# Booster2.net
KiCad netlist of a schematic drawn in Altium Designer
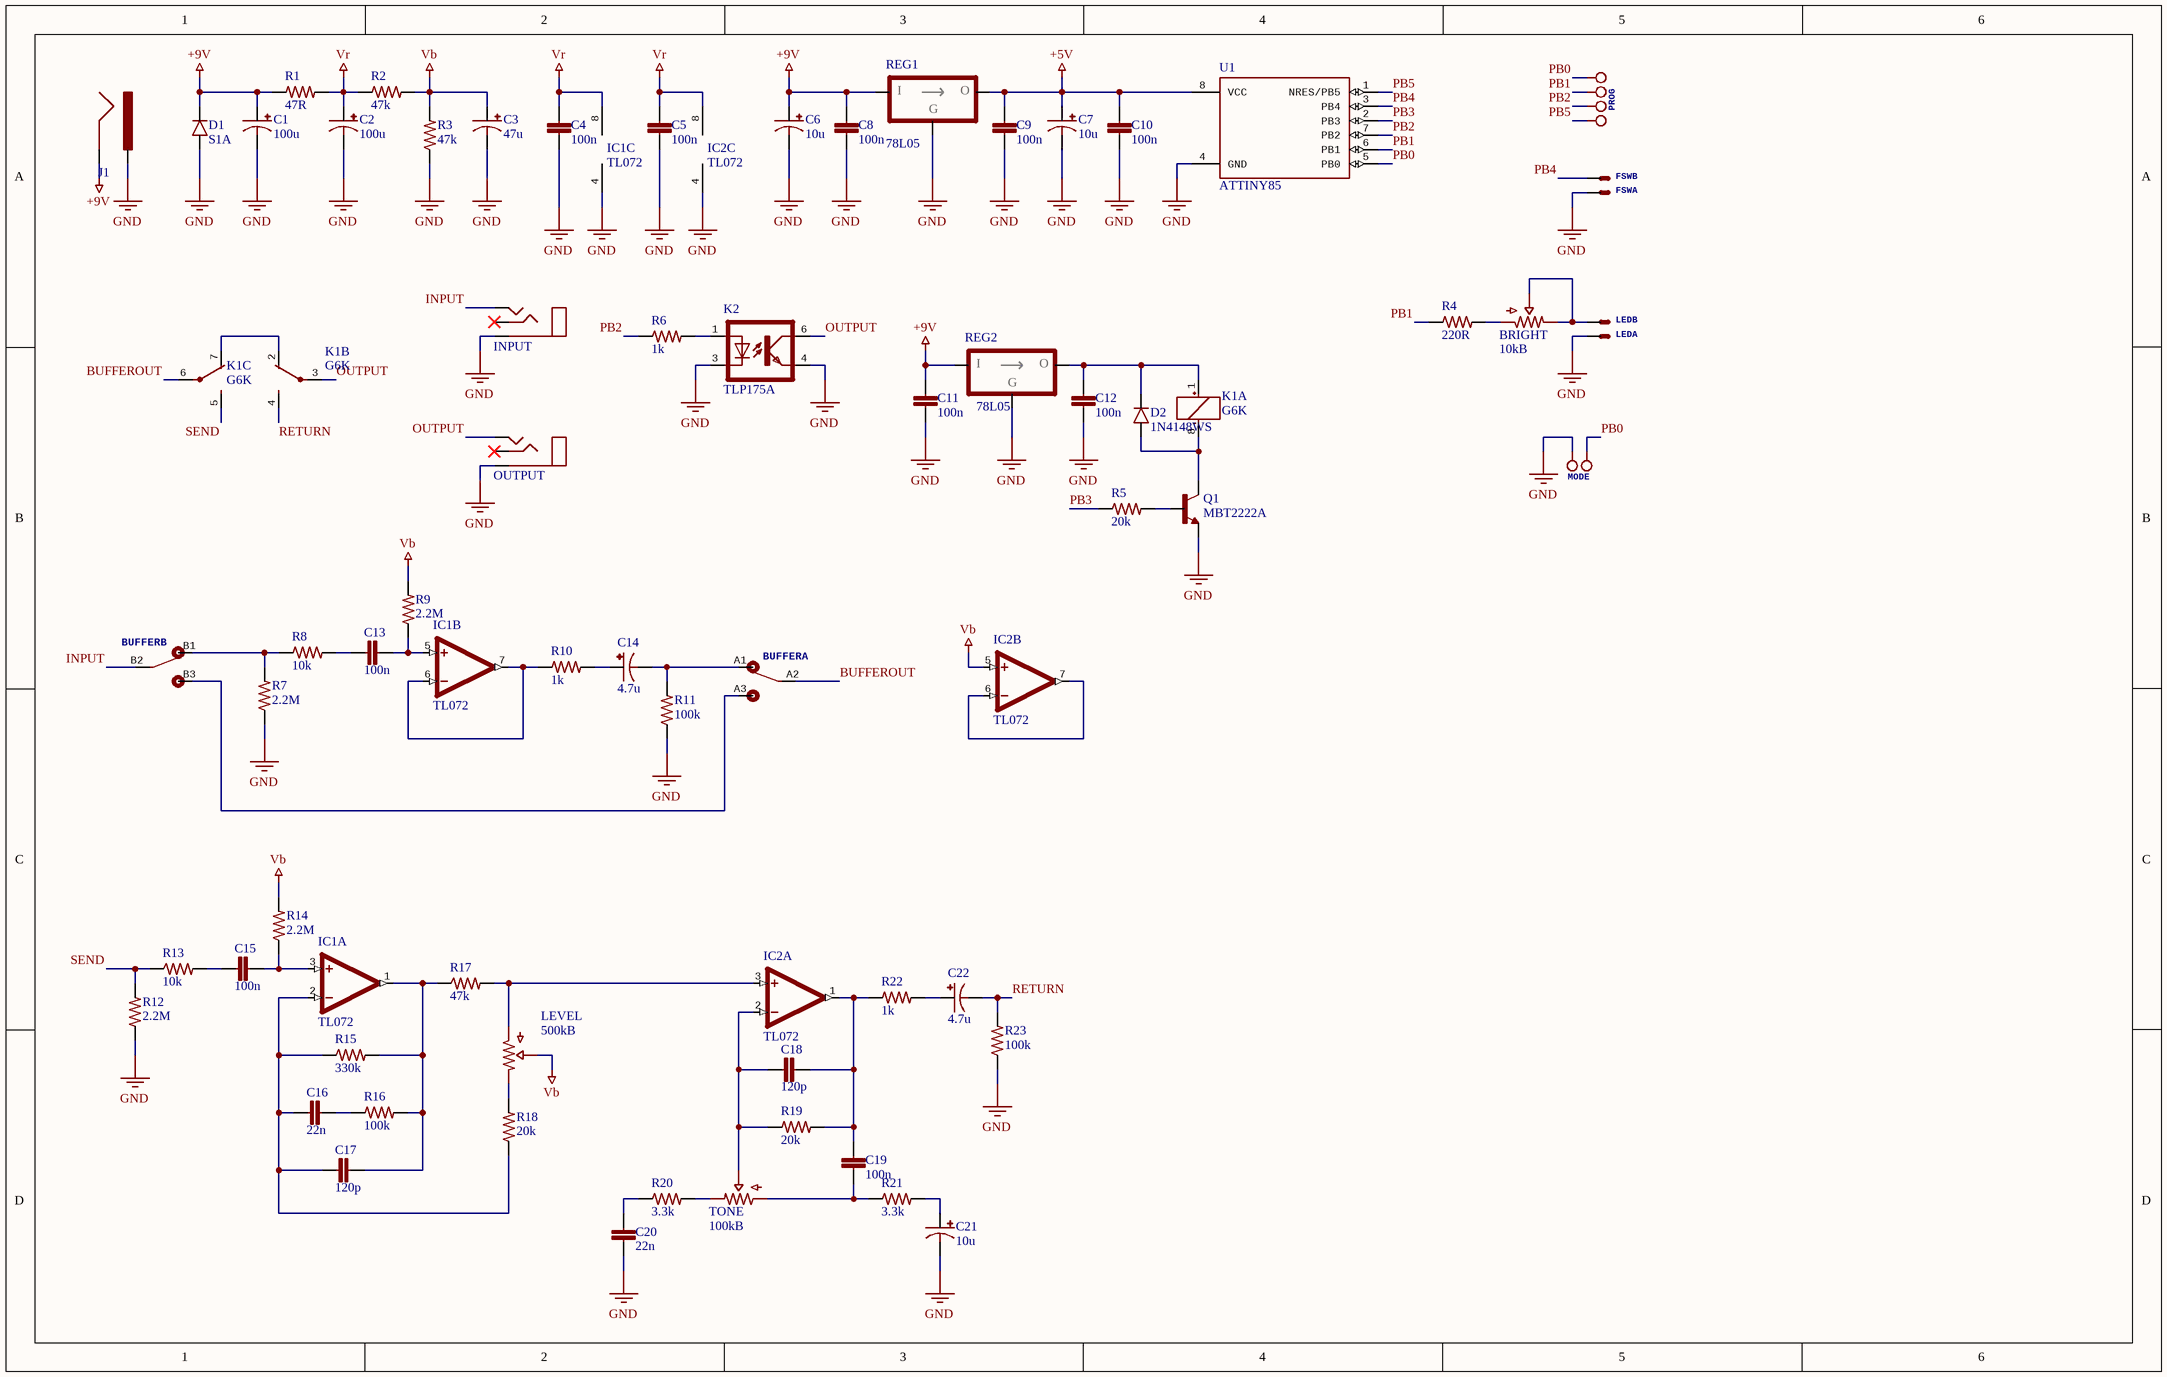
[diagram p0: Booster2.SchDoc]

(export (version "E")
  (design (tool "Eeschema 10.0.6"))
  (components
    (comp (ref "BRIGHT")
      (value "10kB")
      (footprint "BOURNS_3362P")
      (description "10k Lin 3362P trimmer")
      (libsource (lib "Pedals") (part "TRIM_10kB_3362P"))
    )
    (comp (ref "BUFFER")
      (value "DPDT")
      (footprint "DPDT_SLIDE")
      (description "DPDT slide switch ON/ON")
      (libsource (lib "Pedals") (part "SW_SLIDE_DPDT_ON-ON"))
    )
    (comp (ref "C1")
      (value "100u")
      (footprint "CAPAE_D")
      (description "CAP ALUM 100UF 25V SMD")
      (fields
        (field (name "MANUFACTURER") "Multicomp")
        (field (name "MANUFACTURER PART NUMBER") "MCVVT025M101EA6L")
      )
      (libsource (lib "Pedals SMD") (part "MCVVT025M101EA6L"))
    )
    (comp (ref "C2")
      (value "100u")
      (footprint "CAPAE_D")
      (description "CAP ALUM 100UF 25V SMD")
      (fields
        (field (name "MANUFACTURER") "Multicomp")
        (field (name "MANUFACTURER PART NUMBER") "MCVVT025M101EA6L")
      )
      (libsource (lib "Pedals SMD") (part "MCVVT025M101EA6L"))
    )
    (comp (ref "C3")
      (value "47u")
      (footprint "CAPAE_D")
      (description "CAP ALUM 47UF 25V SMD")
      (fields
        (field (name "MANUFACTURER") "Multicomp")
        (field (name "MANUFACTURER PART NUMBER") "MCVVT025M470EA1L")
      )
      (libsource (lib "Pedals SMD") (part "MCVVT025M470EA1L"))
    )
    (comp (ref "C4")
      (value "100n")
      (footprint "CHIP_0603")
      (description "CAP CER 100NF 50V X7R 0603")
      (fields
        (field (name "MANUFACTURER") "Multicomp")
        (field (name "MANUFACTURER PART NUMBER") "MC0603B104K500CT")
      )
      (libsource (lib "Pedals SMD") (part "MC0603B104K500CT"))
    )
    (comp (ref "C5")
      (value "100n")
      (footprint "CHIP_0603")
      (description "CAP CER 100NF 50V X7R 0603")
      (fields
        (field (name "MANUFACTURER") "Multicomp")
        (field (name "MANUFACTURER PART NUMBER") "MC0603B104K500CT")
      )
      (libsource (lib "Pedals SMD") (part "MC0603B104K500CT"))
    )
    (comp (ref "C6")
      (value "10u")
      (footprint "CAPAE_B")
      (description "CAP ALUM 10UF 25V SMD")
      (fields
        (field (name "MANUFACTURER") "Multicomp")
        (field (name "MANUFACTURER PART NUMBER") "MCVVT025M100CA1L")
      )
      (libsource (lib "Pedals SMD") (part "MCVVT025M100CA1L"))
    )
    (comp (ref "C7")
      (value "10u")
      (footprint "CAPAE_B")
      (description "CAP ALUM 10UF 25V SMD")
      (fields
        (field (name "MANUFACTURER") "Multicomp")
        (field (name "MANUFACTURER PART NUMBER") "MCVVT025M100CA1L")
      )
      (libsource (lib "Pedals SMD") (part "MCVVT025M100CA1L"))
    )
    (comp (ref "C8")
      (value "100n")
      (footprint "CHIP_0603")
      (description "CAP CER 100NF 50V X7R 0603")
      (fields
        (field (name "MANUFACTURER") "Multicomp")
        (field (name "MANUFACTURER PART NUMBER") "MC0603B104K500CT")
      )
      (libsource (lib "Pedals SMD") (part "MC0603B104K500CT"))
    )
    (comp (ref "C9")
      (value "100n")
      (footprint "CHIP_0603")
      (description "CAP CER 100NF 50V X7R 0603")
      (fields
        (field (name "MANUFACTURER") "Multicomp")
        (field (name "MANUFACTURER PART NUMBER") "MC0603B104K500CT")
      )
      (libsource (lib "Pedals SMD") (part "MC0603B104K500CT"))
    )
    (comp (ref "C10")
      (value "100n")
      (footprint "CHIP_0603")
      (description "CAP CER 100NF 50V X7R 0603")
      (fields
        (field (name "MANUFACTURER") "Multicomp")
        (field (name "MANUFACTURER PART NUMBER") "MC0603B104K500CT")
      )
      (libsource (lib "Pedals SMD") (part "MC0603B104K500CT"))
    )
    (comp (ref "C11")
      (value "100n")
      (footprint "CHIP_0603")
      (description "CAP CER 100NF 50V X7R 0603")
      (fields
        (field (name "MANUFACTURER") "Multicomp")
        (field (name "MANUFACTURER PART NUMBER") "MC0603B104K500CT")
      )
      (libsource (lib "Pedals SMD") (part "MC0603B104K500CT"))
    )
    (comp (ref "C12")
      (value "100n")
      (footprint "CHIP_0603")
      (description "CAP CER 100NF 50V X7R 0603")
      (fields
        (field (name "MANUFACTURER") "Multicomp")
        (field (name "MANUFACTURER PART NUMBER") "MC0603B104K500CT")
      )
      (libsource (lib "Pedals SMD") (part "MC0603B104K500CT"))
    )
    (comp (ref "C13")
      (value "100n")
      (footprint "CHIP_1206")
      (description "CAP CER 100NF 50V C0G/NP0 1206")
      (fields
        (field (name "MANUFACTURER") "Murata")
        (field (name "MANUFACTURER PART NUMBER") "GRM31C5C1H104JA01L")
      )
      (libsource (lib "Pedals SMD") (part "GRM31C5C1H104JA01L"))
    )
    (comp (ref "C14")
      (value "4.7u")
      (footprint "CAPAE_C")
      (description "CAP ALUM 4.7UF 50V LESR SMD")
      (fields
        (field (name "MANUFACTURER") "Panasonic")
        (field (name "MANUFACTURER PART NUMBER") "EEEFC1H4R7R")
      )
      (libsource (lib "Pedals SMD") (part "EEEFC1H4R7R"))
    )
    (comp (ref "C15")
      (value "100n")
      (footprint "CHIP_1206")
      (description "CAP CER 100NF 50V C0G/NP0 1206")
      (fields
        (field (name "MANUFACTURER") "Murata")
        (field (name "MANUFACTURER PART NUMBER") "GRM31C5C1H104JA01L")
      )
      (libsource (lib "Pedals SMD") (part "GRM31C5C1H104JA01L"))
    )
    (comp (ref "C16")
      (value "22n")
      (footprint "CHIP_0805")
      (description "CAP CER 22NF 50V C0G/NP0 0805")
      (fields
        (field (name "MANUFACTURER") "Murata")
        (field (name "MANUFACTURER PART NUMBER") "GRM21B5C1H223JA01L")
      )
      (libsource (lib "Pedals SMD") (part "GRM21B5C1H223JA01L"))
    )
    (comp (ref "C17")
      (value "120p")
      (footprint "CHIP_0603")
      (description "CAP CER 120PF 50V C0G/NP0 0603")
      (fields
        (field (name "MANUFACTURER") "Multicomp")
        (field (name "MANUFACTURER PART NUMBER") "MC0603N121J500CT")
      )
      (libsource (lib "Pedals SMD") (part "MC0603N121J500CT"))
    )
    (comp (ref "C18")
      (value "120p")
      (footprint "CHIP_0603")
      (description "CAP CER 120PF 50V C0G/NP0 0603")
      (fields
        (field (name "MANUFACTURER") "Multicomp")
        (field (name "MANUFACTURER PART NUMBER") "MC0603N121J500CT")
      )
      (libsource (lib "Pedals SMD") (part "MC0603N121J500CT"))
    )
    (comp (ref "C19")
      (value "100n")
      (footprint "CHIP_1206")
      (description "CAP CER 100NF 50V C0G/NP0 1206")
      (fields
        (field (name "MANUFACTURER") "Murata")
        (field (name "MANUFACTURER PART NUMBER") "GRM31C5C1H104JA01L")
      )
      (libsource (lib "") (part "GRM31C5C1H104JA01L_1"))
    )
    (comp (ref "C20")
      (value "22n")
      (footprint "CHIP_0805")
      (description "CAP CER 22NF 50V C0G/NP0 0805")
      (fields
        (field (name "MANUFACTURER") "Murata")
        (field (name "MANUFACTURER PART NUMBER") "GRM21B5C1H223JA01L")
      )
      (libsource (lib "") (part "GRM21B5C1H223JA01L_1"))
    )
    (comp (ref "C21")
      (value "10u")
      (footprint "CAPAE_D")
      (description "CAP ALUM 10UF 20% 50V LESR SMD")
      (fields
        (field (name "MANUFACTURER") "Panasonic")
        (field (name "MANUFACTURER PART NUMBER") "EEEFC1H100P")
      )
      (libsource (lib "Pedals SMD") (part "EEEFC1H100P"))
    )
    (comp (ref "C22")
      (value "4.7u")
      (footprint "CAPAE_C")
      (description "CAP ALUM 4.7UF 50V LESR SMD")
      (fields
        (field (name "MANUFACTURER") "Panasonic")
        (field (name "MANUFACTURER PART NUMBER") "EEEFC1H4R7R")
      )
      (libsource (lib "Pedals SMD") (part "EEEFC1H4R7R"))
    )
    (comp (ref "D1")
      (value "S1A")
      (footprint "DO214")
      (description "DIODE GEN PURP 50V 1A SMA")
      (fields (field (name "MANUFACTURER") "ON Semiconductor / Fairchild"))
      (libsource (lib "Pedals SMD") (part "S1A"))
    )
    (comp (ref "D2")
      (value "1N4148WS")
      (footprint "SOD323")
      (description "DIODE GEN PURP 75V 150MA SOD323F")
      (fields (field (name "MANUFACTURER") "ON Semiconductor / Fairchild"))
      (libsource (lib "Pedals SMD") (part "1N4148WS"))
    )
    (comp (ref "FSW")
      (value "J_JST-XH-02")
      (footprint "JST-XH-02")
      (description "2 Pins male XH header")
      (libsource (lib "Pedals") (part "J_JST-XH-02"))
    )
    (comp (ref "IC1")
      (value "TL072")
      (footprint "SO-8")
      (description "IC OPAMP JFET 4MHZ 8SO")
      (fields
        (field (name "MANUFACTURER") "STMicroelectronics")
        (field (name "MANUFACTURER PART NUMBER") "TL072CDT")
      )
      (libsource (lib "Pedals SMD") (part "TL072CDT"))
    )
    (comp (ref "IC2")
      (value "TL072")
      (footprint "SO-8")
      (description "IC OPAMP JFET 4MHZ 8SO")
      (fields
        (field (name "MANUFACTURER") "STMicroelectronics")
        (field (name "MANUFACTURER PART NUMBER") "TL072CDT")
      )
      (libsource (lib "Pedals SMD") (part "TL072CDT"))
    )
    (comp (ref "INPUT")
      (value "J_STEREO")
      (footprint "STEREO")
      (description "6.35mm stereo insulated socket jack PCB mounted")
      (libsource (lib "Pedals") (part "J_STEREO"))
    )
    (comp (ref "J1")
      (value "J_DC_JACK")
      (footprint "DC_JACK")
      (description "DC Power jack 2.1mm barrel")
      (libsource (lib "Pedals") (part "J_DC_JACK"))
    )
    (comp (ref "K1")
      (value "G6K")
      (footprint "G6K")
      (description "OMRON - G6K-2F 5DC - RELAY, SIGNAL, DPDT, 30VDC, 1A")
      (fields (field (name "MANUFACTURER") "Cliff") (field (name "MANUFACTURER PART NUMBER") "G6K-2F5DC"))
      (libsource (lib "Pedals SMD") (part "G6K-2F5DC"))
    )
    (comp (ref "K2")
      (value "TLP175A")
      (footprint "TLP175A")
      (description "Toshiba TLP175A AC Input MOSFET Output Optocoupler, Surface Mount, 4-Pin SOIC")
      (fields (field (name "MANUFACTURER") "Toshiba"))
      (libsource (lib "Pedals SMD") (part "TLP175A"))
    )
    (comp (ref "LED")
      (value "J_JST-XH-02")
      (footprint "JST-XH-02")
      (description "2 Pins male XH header")
      (libsource (lib "Pedals") (part "J_JST-XH-02"))
    )
    (comp (ref "LEVEL")
      (value "500kB")
      (footprint "ALPHA_16mm_BOTTOM")
      (description "500k Lin potentiometer round shaft")
      (libsource (lib "Pedals") (part "POT_500kB_ALPHA_16mm"))
    )
    (comp (ref "MODE")
      (value "J_HEADER_2PINS")
      (footprint "HEADER_2PINS")
      (description "2 Pins male header")
      (libsource (lib "Pedals") (part "J_HEADER_2PINS"))
    )
    (comp (ref "OUTPUT")
      (value "J_STEREO")
      (footprint "STEREO")
      (description "6.35mm stereo insulated socket jack PCB mounted")
      (libsource (lib "Pedals") (part "J_STEREO"))
    )
    (comp (ref "PROG")
      (value "J_HEADER_4PINS_FEM")
      (footprint "HEADER_4Pins_FEM")
      (description "4 Pins female header")
      (libsource (lib "Pedals") (part "J_HEADER_4PINS_FEM"))
    )
    (comp (ref "Q1")
      (value "MBT2222A")
      (footprint "SOT23")
      (description "TRANS NPN 40V 0.6A SOT323")
      (fields
        (field (name "MANUFACTURER") "ON Semiconductor")
        (field (name "MANUFACTURER PART NUMBER") "MMBT2222AWT1G")
      )
      (libsource (lib "Pedals SMD") (part "MMBT2222AWT1G"))
    )
    (comp (ref "R1")
      (value "47R")
      (footprint "CHIP_R_1206")
      (description "RES SMD 47 OHM 1% 1/4W 1206")
      (fields
        (field (name "MANUFACTURER") "Vishay")
        (field (name "MANUFACTURER PART NUMBER") "CRCW120647R0FKEA")
      )
      (libsource (lib "Pedals SMD") (part "CRCW120647R0FKEA"))
    )
    (comp (ref "R2")
      (value "47k")
      (footprint "CHIP_R_1206")
      (description "RES SMD 47K OHM 1% 1/4W 1206")
      (fields
        (field (name "MANUFACTURER") "Vishay")
        (field (name "MANUFACTURER PART NUMBER") "CRCW120647K0FKEA")
      )
      (libsource (lib "Pedals SMD") (part "CRCW120647K0FKEA"))
    )
    (comp (ref "R3")
      (value "47k")
      (footprint "CHIP_R_1206")
      (description "RES SMD 47K OHM 1% 1/4W 1206")
      (fields
        (field (name "MANUFACTURER") "Vishay")
        (field (name "MANUFACTURER PART NUMBER") "CRCW120647K0FKEA")
      )
      (libsource (lib "Pedals SMD") (part "CRCW120647K0FKEA"))
    )
    (comp (ref "R4")
      (value "220R")
      (footprint "CHIP_R_1206")
      (description "RES SMD 220 OHM 1% 1/4W 1206")
      (fields
        (field (name "MANUFACTURER") "Vishay")
        (field (name "MANUFACTURER PART NUMBER") "CRCW1206220RFKEA")
      )
      (libsource (lib "Pedals SMD") (part "CRCW1206220RFKEA"))
    )
    (comp (ref "R5")
      (value "20k")
      (footprint "CHIP_R_0603")
      (description "RES SMD 20K OHM 1% 1/10W 0603")
      (fields
        (field (name "MANUFACTURER") "Vishay")
        (field (name "MANUFACTURER PART NUMBER") "CRCW060320K0FKEA")
      )
      (libsource (lib "Pedals SMD") (part "CRCW060320K0FKEA"))
    )
    (comp (ref "R6")
      (value "1k")
      (footprint "CHIP_R_0603")
      (description "RES SMD 1K OHM 1% 1/10W 0603")
      (fields
        (field (name "MANUFACTURER") "Vishay Dale")
        (field (name "MANUFACTURER PART NUMBER") "CRCW06031K00FKEA")
      )
      (libsource (lib "Pedals SMD") (part "CRCW06031K00FKEA"))
    )
    (comp (ref "R7")
      (value "2.2M")
      (footprint "CHIP_R_0603")
      (description "RES SMD 2.2M OHM 1% 1/10W 0603")
      (fields
        (field (name "MANUFACTURER") "Vishay")
        (field (name "MANUFACTURER PART NUMBER") "CRCW06032M20FKEA")
      )
      (libsource (lib "Pedals SMD") (part "CRCW06032M20FKEA"))
    )
    (comp (ref "R8")
      (value "10k")
      (footprint "CHIP_R_0603")
      (description "RES SMD 10K OHM 1% 1/10W 0603")
      (fields
        (field (name "MANUFACTURER") "Vishay")
        (field (name "MANUFACTURER PART NUMBER") "CRCW060310K0FKEA")
      )
      (libsource (lib "Pedals SMD") (part "CRCW060310K0FKEA"))
    )
    (comp (ref "R9")
      (value "2.2M")
      (footprint "CHIP_R_0603")
      (description "RES SMD 2.2M OHM 1% 1/10W 0603")
      (fields
        (field (name "MANUFACTURER") "Vishay")
        (field (name "MANUFACTURER PART NUMBER") "CRCW06032M20FKEA")
      )
      (libsource (lib "Pedals SMD") (part "CRCW06032M20FKEA"))
    )
    (comp (ref "R10")
      (value "1k")
      (footprint "CHIP_R_0603")
      (description "RES SMD 1K OHM 1% 1/10W 0603")
      (fields
        (field (name "MANUFACTURER") "Vishay Dale")
        (field (name "MANUFACTURER PART NUMBER") "CRCW06031K00FKEA")
      )
      (libsource (lib "Pedals SMD") (part "CRCW06031K00FKEA"))
    )
    (comp (ref "R11")
      (value "100k")
      (footprint "CHIP_R_0603")
      (description "RES SMD 100K OHM 1% 1/10W 0603")
      (fields
        (field (name "MANUFACTURER") "Vishay")
        (field (name "MANUFACTURER PART NUMBER") "CRCW0603100KFKEA")
      )
      (libsource (lib "Pedals SMD") (part "CRCW0603100KFKEA"))
    )
    (comp (ref "R12")
      (value "2.2M")
      (footprint "CHIP_R_0603")
      (description "RES SMD 2.2M OHM 1% 1/10W 0603")
      (fields
        (field (name "MANUFACTURER") "Vishay")
        (field (name "MANUFACTURER PART NUMBER") "CRCW06032M20FKEA")
      )
      (libsource (lib "Pedals SMD") (part "CRCW06032M20FKEA"))
    )
    (comp (ref "R13")
      (value "10k")
      (footprint "CHIP_R_0603")
      (description "RES SMD 10K OHM 1% 1/10W 0603")
      (fields
        (field (name "MANUFACTURER") "Vishay")
        (field (name "MANUFACTURER PART NUMBER") "CRCW060310K0FKEA")
      )
      (libsource (lib "Pedals SMD") (part "CRCW060310K0FKEA"))
    )
    (comp (ref "R14")
      (value "2.2M")
      (footprint "CHIP_R_0603")
      (description "RES SMD 2.2M OHM 1% 1/10W 0603")
      (fields
        (field (name "MANUFACTURER") "Vishay")
        (field (name "MANUFACTURER PART NUMBER") "CRCW06032M20FKEA")
      )
      (libsource (lib "Pedals SMD") (part "CRCW06032M20FKEA"))
    )
    (comp (ref "R15")
      (value "330k")
      (footprint "CHIP_R_0603")
      (description "RES SMD 330K OHM 1% 1/10W 0603")
      (fields
        (field (name "MANUFACTURER") "Vishay")
        (field (name "MANUFACTURER PART NUMBER") "CRCW0603330KFKEA")
      )
      (libsource (lib "Pedals SMD") (part "CRCW0603330KFKEA"))
    )
    (comp (ref "R16")
      (value "100k")
      (footprint "CHIP_R_0603")
      (description "RES SMD 100K OHM 1% 1/10W 0603")
      (fields
        (field (name "MANUFACTURER") "Vishay")
        (field (name "MANUFACTURER PART NUMBER") "CRCW0603100KFKEA")
      )
      (libsource (lib "Pedals SMD") (part "CRCW0603100KFKEA"))
    )
    (comp (ref "R17")
      (value "47k")
      (footprint "CHIP_R_0603")
      (description "RES SMD 47K OHM 1% 1/10W 0603")
      (fields
        (field (name "MANUFACTURER") "Vishay")
        (field (name "MANUFACTURER PART NUMBER") "CRCW060347K0FKEA")
      )
      (libsource (lib "Pedals SMD") (part "CRCW060347K0FKEA"))
    )
    (comp (ref "R18")
      (value "20k")
      (footprint "CHIP_R_0603")
      (description "RES SMD 20K OHM 1% 1/10W 0603")
      (fields
        (field (name "MANUFACTURER") "Vishay")
        (field (name "MANUFACTURER PART NUMBER") "CRCW060320K0FKEA")
      )
      (libsource (lib "Pedals SMD") (part "CRCW060320K0FKEA"))
    )
    (comp (ref "R19")
      (value "20k")
      (footprint "CHIP_R_0603")
      (description "RES SMD 20K OHM 1% 1/10W 0603")
      (fields
        (field (name "MANUFACTURER") "Vishay")
        (field (name "MANUFACTURER PART NUMBER") "CRCW060320K0FKEA")
      )
      (libsource (lib "Pedals SMD") (part "CRCW060320K0FKEA"))
    )
    (comp (ref "R20")
      (value "3.3k")
      (footprint "CHIP_R_0603")
      (description "RES SMD 3.3K OHM 1% 1/10W 0603")
      (fields
        (field (name "MANUFACTURER") "Vishay")
        (field (name "MANUFACTURER PART NUMBER") "CRCW06033K30FKEA")
      )
      (libsource (lib "Pedals SMD") (part "CRCW06033K30FKEA"))
    )
    (comp (ref "R21")
      (value "3.3k")
      (footprint "CHIP_R_0603")
      (description "RES SMD 3.3K OHM 1% 1/10W 0603")
      (fields
        (field (name "MANUFACTURER") "Vishay")
        (field (name "MANUFACTURER PART NUMBER") "CRCW06033K30FKEA")
      )
      (libsource (lib "Pedals SMD") (part "CRCW06033K30FKEA"))
    )
    (comp (ref "R22")
      (value "1k")
      (footprint "CHIP_R_0603")
      (description "RES SMD 1K OHM 1% 1/10W 0603")
      (fields
        (field (name "MANUFACTURER") "Vishay Dale")
        (field (name "MANUFACTURER PART NUMBER") "CRCW06031K00FKEA")
      )
      (libsource (lib "Pedals SMD") (part "CRCW06031K00FKEA"))
    )
    (comp (ref "R23")
      (value "100k")
      (footprint "CHIP_R_0603")
      (description "RES SMD 100K OHM 1% 1/10W 0603")
      (fields
        (field (name "MANUFACTURER") "Vishay")
        (field (name "MANUFACTURER PART NUMBER") "CRCW0603100KFKEA")
      )
      (libsource (lib "Pedals SMD") (part "CRCW0603100KFKEA"))
    )
    (comp (ref "REG1")
      (value "78L05")
      (footprint "SOT23-3")
      (description "TAIWAN SEMICONDUCTOR - TS78L05CX RFG - REG 3-TERMINAL 100MA, SMD, SOT23-3")
      (fields
        (field (name "MANUFACTURER") "Taiwan Semiconductor")
        (field (name "MANUFACTURER PART NUMBER") "TS78L05CXRFG")
      )
      (libsource (lib "Pedals SMD") (part "TS78L05CXRFG"))
    )
    (comp (ref "REG2")
      (value "78L05")
      (footprint "SOT23-3")
      (description "TAIWAN SEMICONDUCTOR - TS78L05CX RFG - REG 3-TERMINAL 100MA, SMD, SOT23-3")
      (fields
        (field (name "MANUFACTURER") "Taiwan Semiconductor")
        (field (name "MANUFACTURER PART NUMBER") "TS78L05CXRFG")
      )
      (libsource (lib "Pedals SMD") (part "TS78L05CXRFG"))
    )
    (comp (ref "TONE")
      (value "100kB")
      (footprint "ALPHA_16mm_BOTTOM")
      (description "100k Lin potentiometer round shaft")
      (libsource (lib "Pedals") (part "POT_100kB_ALPHA_16mm"))
    )
    (comp (ref "U1")
      (value "ATTINY85")
      (footprint "SOP8")
      (description "IC, 8BIT MCU, AVR TINY, 20MHZ, 8-SOIC")
      (fields
        (field (name "MANUFACTURER") "Microchip / Atmel")
        (field (name "MANUFACTURER PART NUMBER") "ATTINY85-20SU")
      )
      (libsource (lib "Pedals SMD") (part "ATTINY85-20SU"))
    )
  )
  (nets
    (net (code "1") (name "+5V") (class "Default")
      (node (ref "C10") (pin "1") (pinfunction "1_1") (pintype "passive"))
      (node (ref "C7") (pin "+") (pinfunction "+_+") (pintype "passive"))
      (node (ref "C9") (pin "1") (pinfunction "1_1") (pintype "passive"))
      (node (ref "REG1") (pin "1") (pinfunction "OUTPUT_1") (pintype "power_in"))
      (node (ref "U1") (pin "8") (pinfunction "VCC_8") (pintype "power_in"))
    )
    (net (code "2") (name "+9V") (class "Default")
      (node (ref "C1") (pin "+") (pinfunction "+_+") (pintype "passive"))
      (node (ref "C11") (pin "1") (pinfunction "1_1") (pintype "passive"))
      (node (ref "C6") (pin "+") (pinfunction "+_+") (pintype "passive"))
      (node (ref "C8") (pin "1") (pinfunction "1_1") (pintype "passive"))
      (node (ref "D1") (pin "1") (pinfunction "1_1") (pintype "passive"))
      (node (ref "J1") (pin "GND") (pinfunction "GND_GND") (pintype "passive"))
      (node (ref "R1") (pin "1") (pinfunction "1_1") (pintype "passive"))
      (node (ref "REG1") (pin "2") (pinfunction "INPUT_2") (pintype "power_in"))
      (node (ref "REG2") (pin "2") (pinfunction "INPUT_2") (pintype "power_in"))
    )
    (net (code "3") (name "/BUFFEROUT") (class "Default")
      (node (ref "BUFFER") (pin "A2") (pinfunction "2_A2") (pintype "passive"))
      (node (ref "K1") (pin "6") (pinfunction "P_6") (pintype "passive"))
    )
    (net (code "4") (name "/INPUT") (class "Default")
      (node (ref "BUFFER") (pin "B2") (pinfunction "2_B2") (pintype "passive"))
      (node (ref "INPUT") (pin "T") (pinfunction "T_T") (pintype "passive"))
    )
    (net (code "5") (name "/OUTPUT") (class "Default")
      (node (ref "K1") (pin "3") (pinfunction "P_3") (pintype "passive"))
      (node (ref "K2") (pin "6") (pinfunction "COL_6") (pintype "passive"))
      (node (ref "OUTPUT") (pin "T") (pinfunction "T_T") (pintype "passive"))
    )
    (net (code "6") (name "/PB0") (class "Default")
      (node (ref "MODE") (pin "2") (pinfunction "2_2") (pintype "passive"))
      (node (ref "PROG") (pin "4") (pinfunction "4_4") (pintype "passive"))
      (node (ref "U1") (pin "5") (pinfunction "PB0_5") (pintype "bidirectional"))
    )
    (net (code "7") (name "/PB1") (class "Default")
      (node (ref "PROG") (pin "3") (pinfunction "3_3") (pintype "passive"))
      (node (ref "R4") (pin "1") (pinfunction "1_1") (pintype "passive"))
      (node (ref "U1") (pin "6") (pinfunction "PB1_6") (pintype "bidirectional"))
    )
    (net (code "8") (name "/PB2") (class "Default")
      (node (ref "PROG") (pin "2") (pinfunction "2_2") (pintype "passive"))
      (node (ref "R6") (pin "1") (pinfunction "1_1") (pintype "passive"))
      (node (ref "U1") (pin "7") (pinfunction "PB2_7") (pintype "bidirectional"))
    )
    (net (code "9") (name "/PB3") (class "Default")
      (node (ref "R5") (pin "1") (pinfunction "1_1") (pintype "passive"))
      (node (ref "U1") (pin "2") (pinfunction "PB3_2") (pintype "bidirectional"))
    )
    (net (code "10") (name "/PB4") (class "Default")
      (node (ref "FSW") (pin "1") (pinfunction "S_1") (pintype "passive"))
      (node (ref "U1") (pin "3") (pinfunction "PB4_3") (pintype "bidirectional"))
    )
    (net (code "11") (name "/PB5") (class "Default")
      (node (ref "PROG") (pin "1") (pinfunction "1_1") (pintype "passive"))
      (node (ref "U1") (pin "1") (pinfunction "NRES/PB5_1") (pintype "bidirectional"))
    )
    (net (code "12") (name "/RETURN") (class "Default")
      (node (ref "C22") (pin "-") (pinfunction "-_-") (pintype "passive"))
      (node (ref "K1") (pin "4") (pinfunction "S_4") (pintype "passive"))
      (node (ref "R23") (pin "2") (pinfunction "2_2") (pintype "passive"))
    )
    (net (code "13") (name "/SEND") (class "Default")
      (node (ref "K1") (pin "5") (pinfunction "S_5") (pintype "passive"))
      (node (ref "R12") (pin "2") (pinfunction "2_2") (pintype "passive"))
      (node (ref "R13") (pin "1") (pinfunction "1_1") (pintype "passive"))
    )
    (net (code "14") (name "GND") (class "Default")
      (node (ref "C1") (pin "-") (pinfunction "-_-") (pintype "passive"))
      (node (ref "C10") (pin "2") (pinfunction "2_2") (pintype "passive"))
      (node (ref "C11") (pin "2") (pinfunction "2_2") (pintype "passive"))
      (node (ref "C12") (pin "2") (pinfunction "2_2") (pintype "passive"))
      (node (ref "C2") (pin "-") (pinfunction "-_-") (pintype "passive"))
      (node (ref "C20") (pin "2") (pinfunction "2_2") (pintype "passive"))
      (node (ref "C21") (pin "-") (pinfunction "-_-") (pintype "passive"))
      (node (ref "C3") (pin "-") (pinfunction "-_-") (pintype "passive"))
      (node (ref "C4") (pin "2") (pinfunction "2_2") (pintype "passive"))
      (node (ref "C5") (pin "2") (pinfunction "2_2") (pintype "passive"))
      (node (ref "C6") (pin "-") (pinfunction "-_-") (pintype "passive"))
      (node (ref "C7") (pin "-") (pinfunction "-_-") (pintype "passive"))
      (node (ref "C8") (pin "2") (pinfunction "2_2") (pintype "passive"))
      (node (ref "C9") (pin "2") (pinfunction "2_2") (pintype "passive"))
      (node (ref "D1") (pin "2") (pinfunction "2_2") (pintype "passive"))
      (node (ref "FSW") (pin "2") (pinfunction "S_2") (pintype "passive"))
      (node (ref "IC1") (pin "4") (pinfunction "V-_4") (pintype "power_in"))
      (node (ref "IC2") (pin "4") (pinfunction "V-_4") (pintype "power_in"))
      (node (ref "INPUT") (pin "S") (pinfunction "S_S") (pintype "passive"))
      (node (ref "J1") (pin "PWR") (pinfunction "PWR_PWR") (pintype "passive"))
      (node (ref "K2") (pin "3") (pinfunction "C_3") (pintype "passive"))
      (node (ref "K2") (pin "4") (pinfunction "EMIT_4") (pintype "passive"))
      (node (ref "LED") (pin "2") (pinfunction "S_2") (pintype "passive"))
      (node (ref "MODE") (pin "1") (pinfunction "1_1") (pintype "passive"))
      (node (ref "OUTPUT") (pin "S") (pinfunction "S_S") (pintype "passive"))
      (node (ref "Q1") (pin "2") (pinfunction "E_2") (pintype "passive"))
      (node (ref "R11") (pin "1") (pinfunction "1_1") (pintype "passive"))
      (node (ref "R12") (pin "1") (pinfunction "1_1") (pintype "passive"))
      (node (ref "R23") (pin "1") (pinfunction "1_1") (pintype "passive"))
      (node (ref "R3") (pin "1") (pinfunction "1_1") (pintype "passive"))
      (node (ref "R7") (pin "1") (pinfunction "1_1") (pintype "passive"))
      (node (ref "REG1") (pin "3") (pinfunction "COMMON_3") (pintype "power_in"))
      (node (ref "REG2") (pin "3") (pinfunction "COMMON_3") (pintype "power_in"))
      (node (ref "U1") (pin "4") (pinfunction "GND_4") (pintype "power_in"))
    )
    (net (code "15") (name "Net-(BRIGHT-Pad1)") (class "Default")
      (node (ref "BRIGHT") (pin "1") (pinfunction "1_1") (pintype "passive"))
      (node (ref "R4") (pin "2") (pinfunction "2_2") (pintype "passive"))
    )
    (net (code "16") (name "Net-(BUFFERA-1)") (class "Default")
      (node (ref "BUFFER") (pin "A1") (pinfunction "1_A1") (pintype "passive"))
      (node (ref "C14") (pin "-") (pinfunction "-_-") (pintype "passive"))
      (node (ref "R11") (pin "2") (pinfunction "2_2") (pintype "passive"))
    )
    (net (code "17") (name "Net-(BUFFERA-3)") (class "Default")
      (node (ref "BUFFER") (pin "A3") (pinfunction "3_A3") (pintype "passive"))
      (node (ref "BUFFER") (pin "B3") (pinfunction "3_B3") (pintype "passive"))
    )
    (net (code "18") (name "Net-(BUFFERB-1)") (class "Default")
      (node (ref "BUFFER") (pin "B1") (pinfunction "1_B1") (pintype "passive"))
      (node (ref "R7") (pin "2") (pinfunction "2_2") (pintype "passive"))
      (node (ref "R8") (pin "1") (pinfunction "1_1") (pintype "passive"))
    )
    (net (code "19") (name "Net-(C13-Pad2)") (class "Default")
      (node (ref "C13") (pin "2") (pinfunction "2_2") (pintype "passive"))
      (node (ref "R8") (pin "2") (pinfunction "2_2") (pintype "passive"))
    )
    (net (code "20") (name "Net-(C14-Pad+)") (class "Default")
      (node (ref "C14") (pin "+") (pinfunction "+_+") (pintype "passive"))
      (node (ref "R10") (pin "2") (pinfunction "2_2") (pintype "passive"))
    )
    (net (code "21") (name "Net-(C15-Pad2)") (class "Default")
      (node (ref "C15") (pin "2") (pinfunction "2_2") (pintype "passive"))
      (node (ref "R13") (pin "2") (pinfunction "2_2") (pintype "passive"))
    )
    (net (code "22") (name "Net-(C16-Pad1)") (class "Default")
      (node (ref "C16") (pin "1") (pinfunction "1_1") (pintype "passive"))
      (node (ref "R16") (pin "1") (pinfunction "1_1") (pintype "passive"))
    )
    (net (code "23") (name "Net-(C19-Pad2)") (class "Default")
      (node (ref "C19") (pin "2") (pinfunction "2_2") (pintype "passive"))
      (node (ref "R21") (pin "1") (pinfunction "1_1") (pintype "passive"))
      (node (ref "TONE") (pin "1") (pinfunction "1_1") (pintype "passive"))
    )
    (net (code "24") (name "Net-(C20-Pad1)") (class "Default")
      (node (ref "C20") (pin "1") (pinfunction "1_1") (pintype "passive"))
      (node (ref "R20") (pin "1") (pinfunction "1_1") (pintype "passive"))
    )
    (net (code "25") (name "Net-(C21-Pad+)") (class "Default")
      (node (ref "C21") (pin "+") (pinfunction "+_+") (pintype "passive"))
      (node (ref "R21") (pin "2") (pinfunction "2_2") (pintype "passive"))
    )
    (net (code "26") (name "Net-(C22-Pad+)") (class "Default")
      (node (ref "C22") (pin "+") (pinfunction "+_+") (pintype "passive"))
      (node (ref "R22") (pin "2") (pinfunction "2_2") (pintype "passive"))
    )
    (net (code "27") (name "Net-(IC1A-+IN)") (class "Default")
      (node (ref "C15") (pin "1") (pinfunction "1_1") (pintype "passive"))
      (node (ref "IC1") (pin "3") (pinfunction "+IN_3") (pintype "input"))
      (node (ref "R14") (pin "1") (pinfunction "1_1") (pintype "passive"))
    )
    (net (code "28") (name "Net-(IC1A--IN)") (class "Default")
      (node (ref "C16") (pin "2") (pinfunction "2_2") (pintype "passive"))
      (node (ref "C17") (pin "2") (pinfunction "2_2") (pintype "passive"))
      (node (ref "IC1") (pin "2") (pinfunction "-IN_2") (pintype "input"))
      (node (ref "R15") (pin "1") (pinfunction "1_1") (pintype "passive"))
      (node (ref "R18") (pin "1") (pinfunction "1_1") (pintype "passive"))
    )
    (net (code "29") (name "Net-(IC1A-OUT)") (class "Default")
      (node (ref "C17") (pin "1") (pinfunction "1_1") (pintype "passive"))
      (node (ref "IC1") (pin "1") (pinfunction "OUT_1") (pintype "output"))
      (node (ref "R15") (pin "2") (pinfunction "2_2") (pintype "passive"))
      (node (ref "R16") (pin "2") (pinfunction "2_2") (pintype "passive"))
      (node (ref "R17") (pin "1") (pinfunction "1_1") (pintype "passive"))
    )
    (net (code "30") (name "Net-(IC1B-+IN)") (class "Default")
      (node (ref "C13") (pin "1") (pinfunction "1_1") (pintype "passive"))
      (node (ref "IC1") (pin "5") (pinfunction "+IN_5") (pintype "input"))
      (node (ref "R9") (pin "1") (pinfunction "1_1") (pintype "passive"))
    )
    (net (code "31") (name "Net-(IC1B--IN)") (class "Default")
      (node (ref "IC1") (pin "6") (pinfunction "-IN_6") (pintype "input"))
      (node (ref "IC1") (pin "7") (pinfunction "OUT_7") (pintype "output"))
      (node (ref "R10") (pin "1") (pinfunction "1_1") (pintype "passive"))
    )
    (net (code "32") (name "Net-(IC2A-+IN)") (class "Default")
      (node (ref "IC2") (pin "3") (pinfunction "+IN_3") (pintype "input"))
      (node (ref "LEVEL") (pin "1") (pinfunction "1_1") (pintype "passive"))
      (node (ref "R17") (pin "2") (pinfunction "2_2") (pintype "passive"))
    )
    (net (code "33") (name "Net-(IC2A--IN)") (class "Default")
      (node (ref "C18") (pin "2") (pinfunction "2_2") (pintype "passive"))
      (node (ref "IC2") (pin "2") (pinfunction "-IN_2") (pintype "input"))
      (node (ref "R19") (pin "1") (pinfunction "1_1") (pintype "passive"))
      (node (ref "TONE") (pin "2") (pinfunction "2_2") (pintype "passive"))
    )
    (net (code "34") (name "Net-(IC2A-OUT)") (class "Default")
      (node (ref "C18") (pin "1") (pinfunction "1_1") (pintype "passive"))
      (node (ref "C19") (pin "1") (pinfunction "1_1") (pintype "passive"))
      (node (ref "IC2") (pin "1") (pinfunction "OUT_1") (pintype "output"))
      (node (ref "R19") (pin "2") (pinfunction "2_2") (pintype "passive"))
      (node (ref "R22") (pin "1") (pinfunction "1_1") (pintype "passive"))
    )
    (net (code "35") (name "Net-(IC2B--IN)") (class "Default")
      (node (ref "IC2") (pin "6") (pinfunction "-IN_6") (pintype "input"))
      (node (ref "IC2") (pin "7") (pinfunction "OUT_7") (pintype "output"))
    )
    (net (code "36") (name "Net-(K1A-+)") (class "Default")
      (node (ref "C12") (pin "1") (pinfunction "1_1") (pintype "passive"))
      (node (ref "D2") (pin "1") (pinfunction "1_1") (pintype "passive"))
      (node (ref "K1") (pin "1") (pinfunction "+_1") (pintype "passive"))
      (node (ref "REG2") (pin "1") (pinfunction "OUTPUT_1") (pintype "power_in"))
    )
    (net (code "37") (name "Net-(K1A--)") (class "Default")
      (node (ref "D2") (pin "2") (pinfunction "2_2") (pintype "passive"))
      (node (ref "K1") (pin "8") (pinfunction "-_8") (pintype "passive"))
      (node (ref "Q1") (pin "3") (pinfunction "C_3") (pintype "passive"))
    )
    (net (code "38") (name "Net-(K1B-O)") (class "Default")
      (node (ref "K1") (pin "2") (pinfunction "O_2") (pintype "passive"))
      (node (ref "K1") (pin "7") (pinfunction "O_7") (pintype "passive"))
    )
    (net (code "39") (name "Net-(K2-A)") (class "Default")
      (node (ref "K2") (pin "1") (pinfunction "A_1") (pintype "passive"))
      (node (ref "R6") (pin "2") (pinfunction "2_2") (pintype "passive"))
    )
    (net (code "40") (name "Net-(LEDB-S)") (class "Default")
      (node (ref "BRIGHT") (pin "2") (pinfunction "2_2") (pintype "passive"))
      (node (ref "BRIGHT") (pin "3") (pinfunction "3_3") (pintype "passive"))
      (node (ref "LED") (pin "1") (pinfunction "S_1") (pintype "passive"))
    )
    (net (code "41") (name "Net-(LEVEL-Pad3)") (class "Default")
      (node (ref "LEVEL") (pin "3") (pinfunction "3_3") (pintype "passive"))
      (node (ref "R18") (pin "2") (pinfunction "2_2") (pintype "passive"))
    )
    (net (code "42") (name "Net-(Q1-B)") (class "Default")
      (node (ref "Q1") (pin "1") (pinfunction "B_1") (pintype "passive"))
      (node (ref "R5") (pin "2") (pinfunction "2_2") (pintype "passive"))
    )
    (net (code "43") (name "Net-(R20-Pad2)") (class "Default")
      (node (ref "R20") (pin "2") (pinfunction "2_2") (pintype "passive"))
      (node (ref "TONE") (pin "3") (pinfunction "3_3") (pintype "passive"))
    )
    (net (code "44") (name "Vb") (class "Default")
      (node (ref "C3") (pin "+") (pinfunction "+_+") (pintype "passive"))
      (node (ref "IC2") (pin "5") (pinfunction "+IN_5") (pintype "input"))
      (node (ref "LEVEL") (pin "2") (pinfunction "2_2") (pintype "passive"))
      (node (ref "R14") (pin "2") (pinfunction "2_2") (pintype "passive"))
      (node (ref "R2") (pin "2") (pinfunction "2_2") (pintype "passive"))
      (node (ref "R3") (pin "2") (pinfunction "2_2") (pintype "passive"))
      (node (ref "R9") (pin "2") (pinfunction "2_2") (pintype "passive"))
    )
    (net (code "45") (name "Vr") (class "Default")
      (node (ref "C2") (pin "+") (pinfunction "+_+") (pintype "passive"))
      (node (ref "C4") (pin "1") (pinfunction "1_1") (pintype "passive"))
      (node (ref "C5") (pin "1") (pinfunction "1_1") (pintype "passive"))
      (node (ref "IC1") (pin "8") (pinfunction "V+_8") (pintype "power_in"))
      (node (ref "IC2") (pin "8") (pinfunction "V+_8") (pintype "power_in"))
      (node (ref "R1") (pin "2") (pinfunction "2_2") (pintype "passive"))
      (node (ref "R2") (pin "1") (pinfunction "1_1") (pintype "passive"))
    )
    (net (code "46") (name "unconnected-(INPUT-PadR)") (class "Default")
      (node (ref "INPUT") (pin "R") (pinfunction "R_R") (pintype "passive+no_connect"))
    )
    (net (code "47") (name "unconnected-(OUTPUT-PadR)") (class "Default")
      (node (ref "OUTPUT") (pin "R") (pinfunction "R_R") (pintype "passive+no_connect"))
    )
  )
)
